# TPS63901_BuckBoost_lowIq_3V3_400mA.net
KiCad netlist of a schematic drawn in Altium Designer
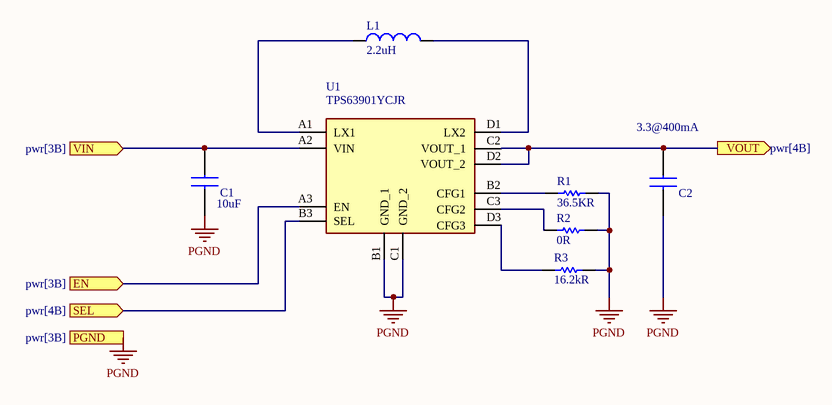
[diagram p0: TPS63901_BuckBoost_lowIq_3V3_400mA.SchDoc]

(export (version "E")
  (design (tool "Eeschema 10.0.6"))
  (components
    (comp (ref "C1")
      (value "10uF")
      (footprint "stm32wl-dev:CAPC1608X90N")
      (description "Multilayer Ceramic Capacitors MLCC - SMD/SMT 10 uF 10 VDC 20% 0603 X5R")
      (fields
        (field (name "MANUFACTURER_PART_NUMBER") "GRM188R61A106MAALJ")
        (field (name "MOUSER PART NUMBER") "81-GRM188R61A106MALJ")
      )
      (libsource (lib "stm32wl-dev") (part "GRM188R61A106MAALJ"))
    )
    (comp (ref "C2")
      (value "GRM188R61A226ME15D")
      (footprint "stm32wl-dev:GRM18x")
      (description "Multilayer Ceramic Capacitors MLCC - SMD/SMT 22 uF 10 VDC 20% 0603 X5R")
      (fields (field (name "MOUSER PART NUMBER") "81-GRM188R61A226ME5D"))
      (libsource (lib "stm32wl-dev") (part "GRM188R61A226ME15D"))
    )
    (comp (ref "L1")
      (value "2.2uH")
      (footprint "DFE2HCAH1R0MJ0L")
      (description "Inductor Power Chip Shielded Wirewound 2.2uH 20% 1MHz Metal 2.3A 0.082Ohm DCR 1008 T/R")
      (fields
        (field (name "MANUFACTURER") "Murata")
        (field (name "MANUFACTURER PART NUMBER") "DFE252012F-2R2M=P2")
      )
      (libsource (lib "stm32wl-dev") (part "DFE252012F-2R2M=P2"))
    )
    (comp (ref "R1")
      (value "36.5KR")
      (footprint "RESC0603X28N")
      (description "Thick Film Resistors - SMD 36.5Kohm 1% 200ppm")
      (fields (field (name "MANUFACTURER_PART_NUMBER") "CRCW020136K5FNED"))
      (libsource (lib "stm32wl-dev") (part "CRCW020136K5FNED"))
    )
    (comp (ref "R2")
      (value "0R")
      (footprint "RESC0603X26N")
      (description "Thick Film Resistors - SMD 0 Ohms 50mW 0201 1%")
      (fields
        (field (name "MANUFACTURER_PART_NUMBER") "RC0201FR-070RL")
        (field (name "MOUSER PART NUMBER") "603-RC0201FR-070RL")
      )
      (libsource (lib "stm32wl-dev") (part "RC0201FR-070RL"))
    )
    (comp (ref "R3")
      (value "16.2kR")
      (footprint "stm32wl-dev:ERJ1GN_(0201)")
      (description "Thick Film Resistors - SMD 0201 16.2Kohm 1% HalogenFree AEC-Q200")
      (fields
        (field (name "MANUFACTURER_PART_NUMBER") "ERJ-1GNF1622C")
        (field (name "MOUSER PART NUMBER") "667-ERJ-1GNF1622C")
      )
      (libsource (lib "stm32wl-dev") (part "ERJ-1GNF1622C"))
    )
    (comp (ref "U1")
      (value "TPS63901YCJR")
      (footprint "BGA12C35P3X4_111X146X35")
      (description "Integrated Circuit")
      (fields (field (name "MOUSER PART NUMBER") "595-TPS63901YCJR"))
      (libsource (lib "stm32wl-dev") (part "TPS63901YCJR"))
    )
  )
  (nets
    (net (code "1") (name "/EN") (class "Default")
      (node (ref "U1") (pin "A3") (pinfunction "EN_A3") (pintype "passive"))
    )
    (net (code "2") (name "/SEL") (class "Default")
      (node (ref "U1") (pin "B3") (pinfunction "SEL_B3") (pintype "passive"))
    )
    (net (code "3") (name "/VIN") (class "Default")
      (node (ref "C1") (pin "1") (pinfunction "1_1") (pintype "passive"))
      (node (ref "U1") (pin "A2") (pinfunction "VIN_A2") (pintype "passive"))
    )
    (net (code "4") (name "/VOUT") (class "Default")
      (node (ref "C2") (pin "1") (pinfunction "1_1") (pintype "passive"))
      (node (ref "U1") (pin "C2") (pinfunction "VOUT_1_C2") (pintype "passive"))
      (node (ref "U1") (pin "D2") (pinfunction "VOUT_2_D2") (pintype "passive"))
    )
    (net (code "5") (name "Net-(U1-CFG1)") (class "Default")
      (node (ref "R1") (pin "1") (pinfunction "1_1") (pintype "passive"))
      (node (ref "U1") (pin "B2") (pinfunction "CFG1_B2") (pintype "passive"))
    )
    (net (code "6") (name "Net-(U1-CFG2)") (class "Default")
      (node (ref "R2") (pin "1") (pinfunction "1_1") (pintype "passive"))
      (node (ref "U1") (pin "C3") (pinfunction "CFG2_C3") (pintype "passive"))
    )
    (net (code "7") (name "Net-(U1-CFG3)") (class "Default")
      (node (ref "R3") (pin "1") (pinfunction "1_1") (pintype "passive"))
      (node (ref "U1") (pin "D3") (pinfunction "CFG3_D3") (pintype "passive"))
    )
    (net (code "8") (name "Net-(U1-LX1)") (class "Default")
      (node (ref "L1") (pin "1") (pinfunction "1_1") (pintype "passive"))
      (node (ref "U1") (pin "A1") (pinfunction "LX1_A1") (pintype "passive"))
    )
    (net (code "9") (name "Net-(U1-LX2)") (class "Default")
      (node (ref "L1") (pin "2") (pinfunction "2_2") (pintype "passive"))
      (node (ref "U1") (pin "D1") (pinfunction "LX2_D1") (pintype "passive"))
    )
    (net (code "10") (name "PGND") (class "Default")
      (node (ref "C1") (pin "2") (pinfunction "2_2") (pintype "passive"))
      (node (ref "C2") (pin "2") (pinfunction "2_2") (pintype "passive"))
      (node (ref "R1") (pin "2") (pinfunction "2_2") (pintype "passive"))
      (node (ref "R2") (pin "2") (pinfunction "2_2") (pintype "passive"))
      (node (ref "R3") (pin "2") (pinfunction "2_2") (pintype "passive"))
      (node (ref "U1") (pin "B1") (pinfunction "GND_1_B1") (pintype "passive"))
      (node (ref "U1") (pin "C1") (pinfunction "GND_2_C1") (pintype "passive"))
    )
  )
)
